# PIC18f26k40_W5500_DevBoard.net
KiCad netlist of a schematic drawn in EAGLE
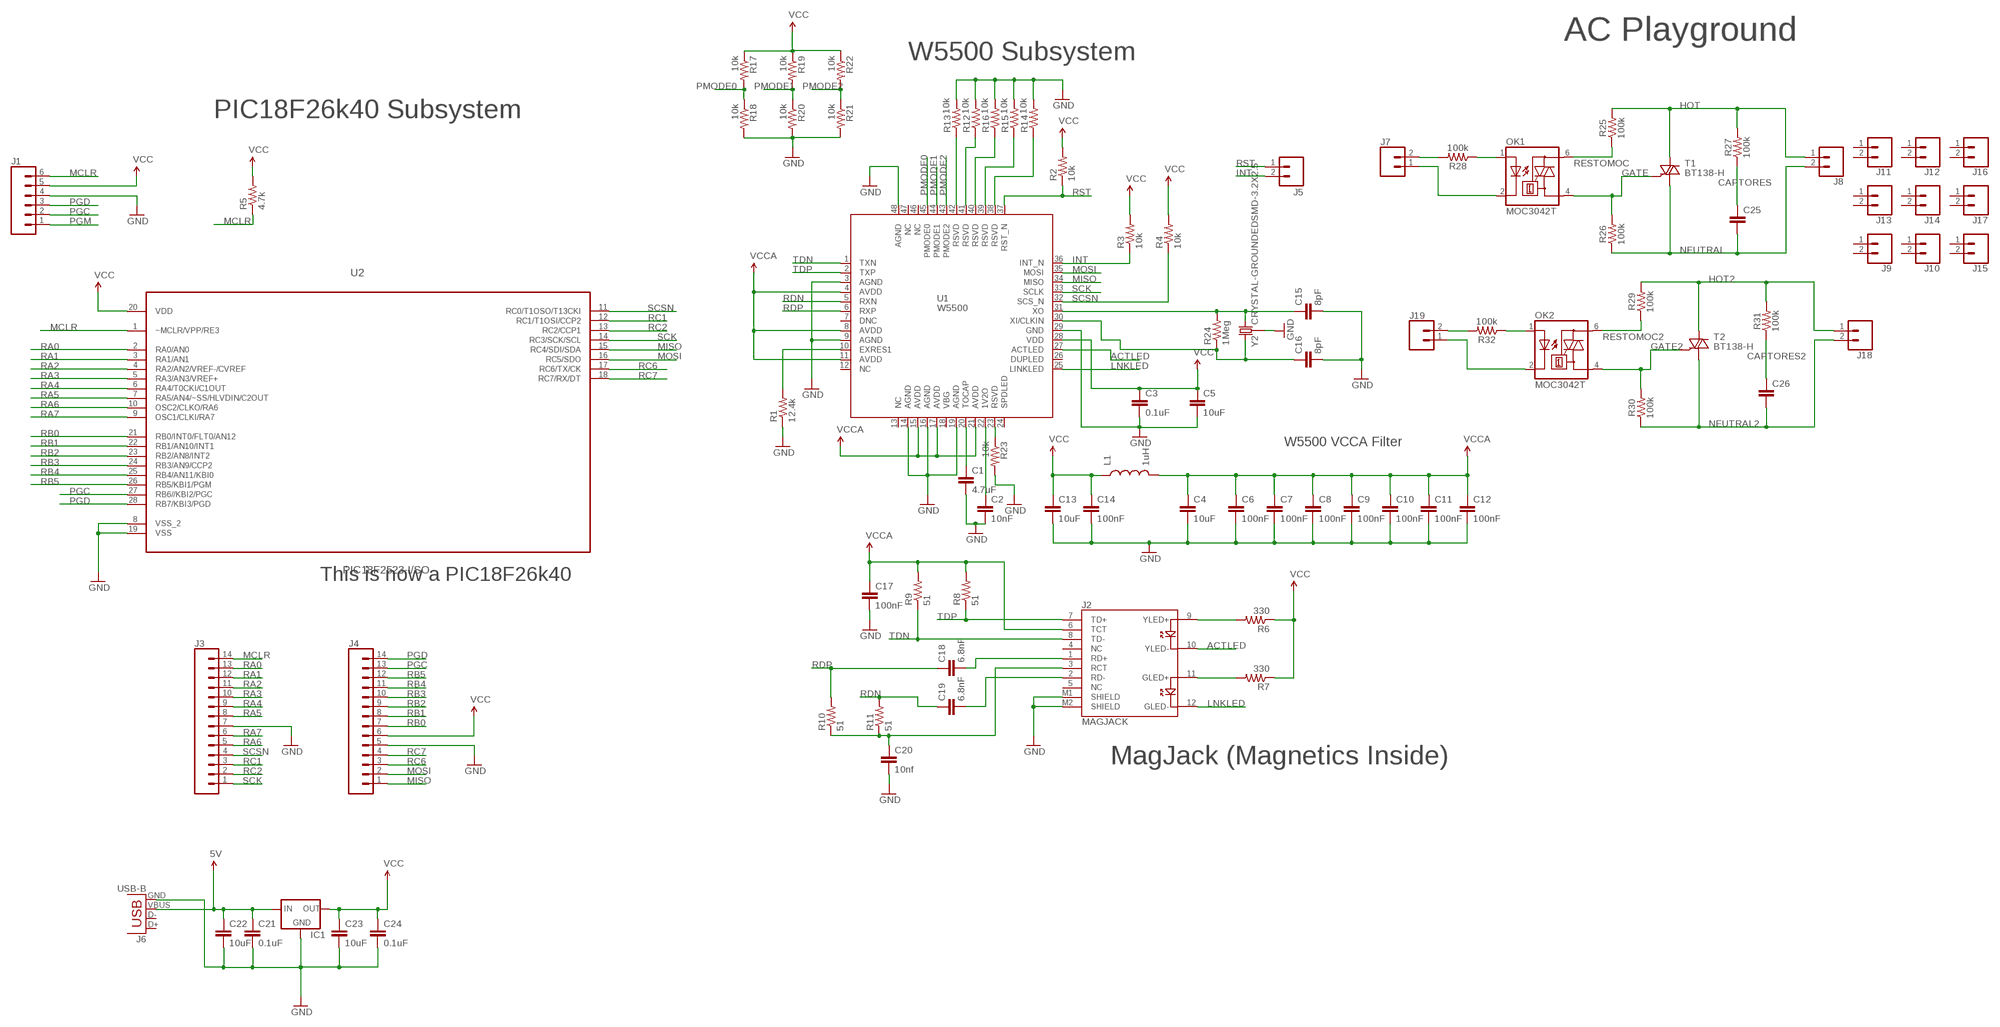
[diagram p0: schematic, sheet 1]

(export (version "E")
  (design (tool "Eeschema 10.0.6"))
  (components
    (comp (ref "C1")
      (value "4.7uF")
      (footprint "eagle-import:0603-CAP")
      (libsource (lib "eagle-import") (part "SparkFun-Passives_CAP0603-CAP"))
    )
    (comp (ref "C2")
      (value "10nF")
      (footprint "eagle-import:0603-CAP")
      (libsource (lib "eagle-import") (part "SparkFun-Passives_CAP0603-CAP"))
    )
    (comp (ref "C3")
      (value "0.1uF")
      (footprint "eagle-import:0603-CAP")
      (libsource (lib "eagle-import") (part "SparkFun-Passives_CAP0603-CAP"))
    )
    (comp (ref "C4")
      (value "10uF")
      (footprint "eagle-import:0603-CAP")
      (libsource (lib "eagle-import") (part "SparkFun-Passives_CAP0603-CAP"))
    )
    (comp (ref "C5")
      (value "10uF")
      (footprint "eagle-import:0603-CAP")
      (libsource (lib "eagle-import") (part "SparkFun-Passives_CAP0603-CAP"))
    )
    (comp (ref "C6")
      (value "100nF")
      (footprint "eagle-import:0603-CAP")
      (libsource (lib "eagle-import") (part "SparkFun-Passives_CAP0603-CAP"))
    )
    (comp (ref "C7")
      (value "100nF")
      (footprint "eagle-import:0603-CAP")
      (libsource (lib "eagle-import") (part "SparkFun-Passives_CAP0603-CAP"))
    )
    (comp (ref "C8")
      (value "100nF")
      (footprint "eagle-import:0603-CAP")
      (libsource (lib "eagle-import") (part "SparkFun-Passives_CAP0603-CAP"))
    )
    (comp (ref "C9")
      (value "100nF")
      (footprint "eagle-import:0603-CAP")
      (libsource (lib "eagle-import") (part "SparkFun-Passives_CAP0603-CAP"))
    )
    (comp (ref "C10")
      (value "100nF")
      (footprint "eagle-import:0603-CAP")
      (libsource (lib "eagle-import") (part "SparkFun-Passives_CAP0603-CAP"))
    )
    (comp (ref "C11")
      (value "100nF")
      (footprint "eagle-import:0603-CAP")
      (libsource (lib "eagle-import") (part "SparkFun-Passives_CAP0603-CAP"))
    )
    (comp (ref "C12")
      (value "100nF")
      (footprint "eagle-import:0603-CAP")
      (libsource (lib "eagle-import") (part "SparkFun-Passives_CAP0603-CAP"))
    )
    (comp (ref "C13")
      (value "10uF")
      (footprint "eagle-import:0603-CAP")
      (libsource (lib "eagle-import") (part "SparkFun-Passives_CAP0603-CAP"))
    )
    (comp (ref "C14")
      (value "100nF")
      (footprint "eagle-import:0603-CAP")
      (libsource (lib "eagle-import") (part "SparkFun-Passives_CAP0603-CAP"))
    )
    (comp (ref "C15")
      (value "8pF")
      (footprint "eagle-import:0603-CAP")
      (libsource (lib "eagle-import") (part "SparkFun-Passives_CAP0603-CAP"))
    )
    (comp (ref "C16")
      (value "8pF")
      (footprint "eagle-import:0603-CAP")
      (libsource (lib "eagle-import") (part "SparkFun-Passives_CAP0603-CAP"))
    )
    (comp (ref "C17")
      (value "100nF")
      (footprint "eagle-import:0603-CAP")
      (libsource (lib "eagle-import") (part "SparkFun-Passives_CAP0603-CAP"))
    )
    (comp (ref "C18")
      (value "6.8nF")
      (footprint "eagle-import:0603-CAP")
      (libsource (lib "eagle-import") (part "SparkFun-Passives_CAP0603-CAP"))
    )
    (comp (ref "C19")
      (value "6.8nF")
      (footprint "eagle-import:0603-CAP")
      (libsource (lib "eagle-import") (part "SparkFun-Passives_CAP0603-CAP"))
    )
    (comp (ref "C20")
      (value "10nf")
      (footprint "eagle-import:0603-CAP")
      (libsource (lib "eagle-import") (part "SparkFun-Passives_CAP0603-CAP"))
    )
    (comp (ref "C21")
      (value "0.1uF")
      (footprint "eagle-import:0603-CAP")
      (libsource (lib "eagle-import") (part "SparkFun-Passives_CAP0603-CAP"))
    )
    (comp (ref "C22")
      (value "10uF")
      (footprint "eagle-import:0603-CAP")
      (libsource (lib "eagle-import") (part "SparkFun-Passives_CAP0603-CAP"))
    )
    (comp (ref "C23")
      (value "10uF")
      (footprint "eagle-import:0603-CAP")
      (libsource (lib "eagle-import") (part "SparkFun-Passives_CAP0603-CAP"))
    )
    (comp (ref "C24")
      (value "0.1uF")
      (footprint "eagle-import:0603-CAP")
      (libsource (lib "eagle-import") (part "SparkFun-Passives_CAP0603-CAP"))
    )
    (comp (ref "C25")
      (value "CAPPTH3")
      (footprint "eagle-import:CAP-PTH-LARGE")
      (libsource (lib "eagle-import") (part "CAPPTH3"))
    )
    (comp (ref "C26")
      (value "CAPPTH3")
      (footprint "eagle-import:CAP-PTH-LARGE")
      (libsource (lib "eagle-import") (part "CAPPTH3"))
    )
    (comp (ref "IC1")
      (value "78XXL")
      (footprint "eagle-import:78XXL")
      (libsource (lib "eagle-import") (part "78XXL"))
    )
    (comp (ref "J1")
      (value "CONN_06NO_SILK_FEMALE_PTH")
      (footprint "eagle-import:1X06_NO_SILK")
      (libsource (lib "eagle-import") (part "CONN_06NO_SILK_FEMALE_PTH"))
    )
    (comp (ref "J2")
      (value "MAGJACK")
      (footprint "eagle-import:MAGJACK")
      (libsource (lib "eagle-import") (part "MAGJACK"))
    )
    (comp (ref "J3")
      (value "CONN_14")
      (footprint "eagle-import:1X14")
      (libsource (lib "eagle-import") (part "CONN_14"))
    )
    (comp (ref "J4")
      (value "CONN_14")
      (footprint "eagle-import:1X14")
      (libsource (lib "eagle-import") (part "CONN_14"))
    )
    (comp (ref "J5")
      (value "M02PTH")
      (footprint "eagle-import:1X02@1")
      (libsource (lib "eagle-import") (part "M02PTH"))
    )
    (comp (ref "J6")
      (value "USB-B")
      (footprint "eagle-import:USB-B-PTH")
      (libsource (lib "eagle-import") (part "USBPTH"))
    )
    (comp (ref "J7")
      (value "CONN_02")
      (footprint "eagle-import:1X02")
      (libsource (lib "eagle-import") (part "CONN_02"))
    )
    (comp (ref "J8")
      (value "CONN_025MM")
      (footprint "eagle-import:SCREWTERMINAL-5MM-2")
      (libsource (lib "eagle-import") (part "CONN_025MM"))
    )
    (comp (ref "J9")
      (value "CONN_025MM")
      (footprint "eagle-import:SCREWTERMINAL-5MM-2")
      (libsource (lib "eagle-import") (part "CONN_025MM"))
    )
    (comp (ref "J10")
      (value "CONN_025MM")
      (footprint "eagle-import:SCREWTERMINAL-5MM-2")
      (libsource (lib "eagle-import") (part "CONN_025MM"))
    )
    (comp (ref "J11")
      (value "CONN_025MM")
      (footprint "eagle-import:SCREWTERMINAL-5MM-2")
      (libsource (lib "eagle-import") (part "CONN_025MM"))
    )
    (comp (ref "J12")
      (value "CONN_025MM")
      (footprint "eagle-import:SCREWTERMINAL-5MM-2")
      (libsource (lib "eagle-import") (part "CONN_025MM"))
    )
    (comp (ref "J13")
      (value "CONN_025MM")
      (footprint "eagle-import:SCREWTERMINAL-5MM-2")
      (libsource (lib "eagle-import") (part "CONN_025MM"))
    )
    (comp (ref "J14")
      (value "CONN_025MM")
      (footprint "eagle-import:SCREWTERMINAL-5MM-2")
      (libsource (lib "eagle-import") (part "CONN_025MM"))
    )
    (comp (ref "J15")
      (value "CONN_025MM")
      (footprint "eagle-import:SCREWTERMINAL-5MM-2")
      (libsource (lib "eagle-import") (part "CONN_025MM"))
    )
    (comp (ref "J16")
      (value "CONN_025MM")
      (footprint "eagle-import:SCREWTERMINAL-5MM-2")
      (libsource (lib "eagle-import") (part "CONN_025MM"))
    )
    (comp (ref "J17")
      (value "CONN_025MM")
      (footprint "eagle-import:SCREWTERMINAL-5MM-2")
      (libsource (lib "eagle-import") (part "CONN_025MM"))
    )
    (comp (ref "J18")
      (value "CONN_025MM")
      (footprint "eagle-import:SCREWTERMINAL-5MM-2")
      (libsource (lib "eagle-import") (part "CONN_025MM"))
    )
    (comp (ref "J19")
      (value "CONN_02")
      (footprint "eagle-import:1X02")
      (libsource (lib "eagle-import") (part "CONN_02"))
    )
    (comp (ref "L1")
      (value "1uH")
      (footprint "eagle-import:0603")
      (libsource (lib "eagle-import") (part "INDUCTOR0603"))
    )
    (comp (ref "OK1")
      (value "MOC3042T")
      (footprint "eagle-import:DIL06B")
      (libsource (lib "eagle-import") (part "MOC30T42"))
    )
    (comp (ref "OK2")
      (value "MOC3042T")
      (footprint "eagle-import:DIL06B")
      (libsource (lib "eagle-import") (part "MOC30T42"))
    )
    (comp (ref "R1")
      (value "12.4k")
      (footprint "eagle-import:0603-RES")
      (libsource (lib "eagle-import") (part "RESISTOR0603-RES"))
    )
    (comp (ref "R2")
      (value "10k")
      (footprint "eagle-import:0603-RES")
      (libsource (lib "eagle-import") (part "RESISTOR0603-RES"))
    )
    (comp (ref "R3")
      (value "10k")
      (footprint "eagle-import:0603-RES")
      (libsource (lib "eagle-import") (part "RESISTOR0603-RES"))
    )
    (comp (ref "R4")
      (value "10k")
      (footprint "eagle-import:0603-RES")
      (libsource (lib "eagle-import") (part "RESISTOR0603-RES"))
    )
    (comp (ref "R5")
      (value "4.7k")
      (footprint "eagle-import:0603-RES")
      (libsource (lib "eagle-import") (part "RESISTOR0603-RES"))
    )
    (comp (ref "R6")
      (value "330")
      (footprint "eagle-import:0603-RES")
      (libsource (lib "eagle-import") (part "RESISTOR0603-RES"))
    )
    (comp (ref "R7")
      (value "330")
      (footprint "eagle-import:0603-RES")
      (libsource (lib "eagle-import") (part "RESISTOR0603-RES"))
    )
    (comp (ref "R8")
      (value "51")
      (footprint "eagle-import:0603-RES")
      (libsource (lib "eagle-import") (part "RESISTOR0603-RES"))
    )
    (comp (ref "R9")
      (value "51")
      (footprint "eagle-import:0603-RES")
      (libsource (lib "eagle-import") (part "RESISTOR0603-RES"))
    )
    (comp (ref "R10")
      (value "51")
      (footprint "eagle-import:0603-RES")
      (libsource (lib "eagle-import") (part "RESISTOR0603-RES"))
    )
    (comp (ref "R11")
      (value "51")
      (footprint "eagle-import:0603-RES")
      (libsource (lib "eagle-import") (part "RESISTOR0603-RES"))
    )
    (comp (ref "R12")
      (value "10k")
      (footprint "eagle-import:0603-RES")
      (libsource (lib "eagle-import") (part "RESISTOR0603-RES"))
    )
    (comp (ref "R13")
      (value "10k")
      (footprint "eagle-import:0603-RES")
      (libsource (lib "eagle-import") (part "RESISTOR0603-RES"))
    )
    (comp (ref "R14")
      (value "10k")
      (footprint "eagle-import:0603-RES")
      (libsource (lib "eagle-import") (part "RESISTOR0603-RES"))
    )
    (comp (ref "R15")
      (value "10k")
      (footprint "eagle-import:0603-RES")
      (libsource (lib "eagle-import") (part "RESISTOR0603-RES"))
    )
    (comp (ref "R16")
      (value "10k")
      (footprint "eagle-import:0603-RES")
      (libsource (lib "eagle-import") (part "RESISTOR0603-RES"))
    )
    (comp (ref "R17")
      (value "10k")
      (footprint "eagle-import:0603-RES")
      (libsource (lib "eagle-import") (part "RESISTOR0603-RES"))
    )
    (comp (ref "R18")
      (value "10k")
      (footprint "eagle-import:0603-RES")
      (libsource (lib "eagle-import") (part "RESISTOR0603-RES"))
    )
    (comp (ref "R19")
      (value "10k")
      (footprint "eagle-import:0603-RES")
      (libsource (lib "eagle-import") (part "RESISTOR0603-RES"))
    )
    (comp (ref "R20")
      (value "10k")
      (footprint "eagle-import:0603-RES")
      (libsource (lib "eagle-import") (part "RESISTOR0603-RES"))
    )
    (comp (ref "R21")
      (value "10k")
      (footprint "eagle-import:0603-RES")
      (libsource (lib "eagle-import") (part "RESISTOR0603-RES"))
    )
    (comp (ref "R22")
      (value "10k")
      (footprint "eagle-import:0603-RES")
      (libsource (lib "eagle-import") (part "RESISTOR0603-RES"))
    )
    (comp (ref "R23")
      (value "10k")
      (footprint "eagle-import:0603-RES")
      (libsource (lib "eagle-import") (part "RESISTOR0603-RES"))
    )
    (comp (ref "R24")
      (value "1Meg")
      (footprint "eagle-import:0603-RES")
      (libsource (lib "eagle-import") (part "RESISTOR0603-RES"))
    )
    (comp (ref "R25")
      (value "100k")
      (footprint "eagle-import:AXIAL-0.3")
      (libsource (lib "eagle-import") (part "100KOHM-HORIZ-1/4W-1%"))
    )
    (comp (ref "R26")
      (value "100k")
      (footprint "eagle-import:AXIAL-0.3")
      (libsource (lib "eagle-import") (part "100KOHM-HORIZ-1/4W-1%"))
    )
    (comp (ref "R27")
      (value "100k")
      (footprint "eagle-import:AXIAL-0.3")
      (libsource (lib "eagle-import") (part "100KOHM-HORIZ-1/4W-1%"))
    )
    (comp (ref "R28")
      (value "100k")
      (footprint "eagle-import:AXIAL-0.3")
      (libsource (lib "eagle-import") (part "100KOHM-HORIZ-1/4W-1%"))
    )
    (comp (ref "R29")
      (value "100k")
      (footprint "eagle-import:AXIAL-0.3")
      (libsource (lib "eagle-import") (part "100KOHM-HORIZ-1/4W-1%"))
    )
    (comp (ref "R30")
      (value "100k")
      (footprint "eagle-import:AXIAL-0.3")
      (libsource (lib "eagle-import") (part "100KOHM-HORIZ-1/4W-1%"))
    )
    (comp (ref "R31")
      (value "100k")
      (footprint "eagle-import:AXIAL-0.3")
      (libsource (lib "eagle-import") (part "100KOHM-HORIZ-1/4W-1%"))
    )
    (comp (ref "R32")
      (value "100k")
      (footprint "eagle-import:AXIAL-0.3")
      (libsource (lib "eagle-import") (part "100KOHM-HORIZ-1/4W-1%"))
    )
    (comp (ref "T1")
      (value "BT138-H")
      (footprint "eagle-import:TO220BH")
      (libsource (lib "eagle-import") (part "BT138-H"))
    )
    (comp (ref "T2")
      (value "BT138-H")
      (footprint "eagle-import:TO220BH")
      (libsource (lib "eagle-import") (part "BT138-H"))
    )
    (comp (ref "U1")
      (value "W5500")
      (footprint "eagle-import:W5500")
      (libsource (lib "eagle-import") (part "W5500"))
    )
    (comp (ref "U2")
      (value "PIC18F2523-I/SO")
      (footprint "eagle-import:SOIC127P1030X265-28N")
      (libsource (lib "eagle-import") (part "PIC18F2523-I/SO"))
    )
    (comp (ref "Y2")
      (value "CRYSTAL-GROUNDEDSMD-3.2X2.5")
      (footprint "eagle-import:CRYSTAL-SMD-3.2X2.5MM")
      (libsource (lib "eagle-import") (part "CRYSTAL-GROUNDEDSMD-3.2X2.5"))
    )
  )
  (nets
    (net (code "1") (name "/ACTLED") (class "Default")
      (node (ref "J2") (pin "10") (pinfunction "YLED-_10") (pintype "bidirectional"))
      (node (ref "U1") (pin "27") (pinfunction "ACTLED_27") (pintype "passive"))
    )
    (net (code "2") (name "/CAPTORES") (class "Default")
      (node (ref "C25") (pin "1") (pinfunction "1_1") (pintype "passive"))
      (node (ref "R27") (pin "P$1") (pinfunction "1_P$1") (pintype "passive"))
    )
    (net (code "3") (name "/CAPTORES2") (class "Default")
      (node (ref "C26") (pin "1") (pinfunction "1_1") (pintype "passive"))
      (node (ref "R31") (pin "P$1") (pinfunction "1_P$1") (pintype "passive"))
    )
    (net (code "4") (name "/GATE") (class "Default")
      (node (ref "OK1") (pin "4") (pinfunction "A1_4") (pintype "passive"))
      (node (ref "R26") (pin "P$2") (pinfunction "2_P$2") (pintype "passive"))
      (node (ref "T1") (pin "G") (pinfunction "G_G") (pintype "passive"))
    )
    (net (code "5") (name "/GATE2") (class "Default")
      (node (ref "OK2") (pin "4") (pinfunction "A1_4") (pintype "passive"))
      (node (ref "R30") (pin "P$2") (pinfunction "2_P$2") (pintype "passive"))
      (node (ref "T2") (pin "G") (pinfunction "G_G") (pintype "passive"))
    )
    (net (code "6") (name "/HOT") (class "Default")
      (node (ref "J8") (pin "1") (pinfunction "1_1") (pintype "passive"))
      (node (ref "R25") (pin "P$2") (pinfunction "2_P$2") (pintype "passive"))
      (node (ref "R27") (pin "P$2") (pinfunction "2_P$2") (pintype "passive"))
      (node (ref "T1") (pin "T2") (pinfunction "A2_T2") (pintype "passive"))
    )
    (net (code "7") (name "/HOT2") (class "Default")
      (node (ref "J18") (pin "1") (pinfunction "1_1") (pintype "passive"))
      (node (ref "R29") (pin "P$2") (pinfunction "2_P$2") (pintype "passive"))
      (node (ref "R31") (pin "P$2") (pinfunction "2_P$2") (pintype "passive"))
      (node (ref "T2") (pin "T2") (pinfunction "A2_T2") (pintype "passive"))
    )
    (net (code "8") (name "/INT") (class "Default")
      (node (ref "J5") (pin "2") (pinfunction "2_2") (pintype "passive"))
      (node (ref "R3") (pin "1") (pinfunction "1_1") (pintype "passive"))
      (node (ref "U1") (pin "36") (pinfunction "INT_N_36") (pintype "passive"))
    )
    (net (code "9") (name "/LNKLED") (class "Default")
      (node (ref "J2") (pin "12") (pinfunction "GLED-_12") (pintype "bidirectional"))
      (node (ref "U1") (pin "25") (pinfunction "LINKLED_25") (pintype "passive"))
    )
    (net (code "10") (name "/MCLR") (class "Default")
      (node (ref "J1") (pin "6") (pinfunction "6_6") (pintype "passive"))
      (node (ref "J3") (pin "14") (pinfunction "14_14") (pintype "passive"))
      (node (ref "R5") (pin "1") (pinfunction "1_1") (pintype "passive"))
      (node (ref "U2") (pin "1") (pinfunction "~{MCLR/VPP/RE3}_1") (pintype "input"))
    )
    (net (code "11") (name "/MISO") (class "Default")
      (node (ref "J4") (pin "1") (pinfunction "1_1") (pintype "passive"))
      (node (ref "U1") (pin "34") (pinfunction "MISO_34") (pintype "passive"))
      (node (ref "U2") (pin "15") (pinfunction "RC4/SDI/SDA_15") (pintype "bidirectional"))
    )
    (net (code "12") (name "/MOSI") (class "Default")
      (node (ref "J4") (pin "2") (pinfunction "2_2") (pintype "passive"))
      (node (ref "U1") (pin "35") (pinfunction "MOSI_35") (pintype "passive"))
      (node (ref "U2") (pin "16") (pinfunction "RC5/SDO_16") (pintype "bidirectional"))
    )
    (net (code "13") (name "/NEUTRAL") (class "Default")
      (node (ref "C25") (pin "2") (pinfunction "2_2") (pintype "passive"))
      (node (ref "J8") (pin "2") (pinfunction "2_2") (pintype "passive"))
      (node (ref "R26") (pin "P$1") (pinfunction "1_P$1") (pintype "passive"))
      (node (ref "T1") (pin "T1") (pinfunction "A1_T1") (pintype "passive"))
    )
    (net (code "14") (name "/NEUTRAL2") (class "Default")
      (node (ref "C26") (pin "2") (pinfunction "2_2") (pintype "passive"))
      (node (ref "J18") (pin "2") (pinfunction "2_2") (pintype "passive"))
      (node (ref "R30") (pin "P$1") (pinfunction "1_P$1") (pintype "passive"))
      (node (ref "T2") (pin "T1") (pinfunction "A1_T1") (pintype "passive"))
    )
    (net (code "15") (name "/PGC") (class "Default")
      (node (ref "J1") (pin "2") (pinfunction "2_2") (pintype "passive"))
      (node (ref "J4") (pin "13") (pinfunction "13_13") (pintype "passive"))
      (node (ref "U2") (pin "27") (pinfunction "RB6//KBI2/PGC_27") (pintype "bidirectional"))
    )
    (net (code "16") (name "/PGD") (class "Default")
      (node (ref "J1") (pin "3") (pinfunction "3_3") (pintype "passive"))
      (node (ref "J4") (pin "14") (pinfunction "14_14") (pintype "passive"))
      (node (ref "U2") (pin "28") (pinfunction "RB7/KBI3/PGD_28") (pintype "bidirectional"))
    )
    (net (code "17") (name "/PGM") (class "Default")
      (node (ref "J1") (pin "1") (pinfunction "1_1") (pintype "passive"))
    )
    (net (code "18") (name "/PMODE0") (class "Default")
      (node (ref "R17") (pin "2") (pinfunction "2_2") (pintype "passive"))
      (node (ref "R18") (pin "1") (pinfunction "1_1") (pintype "passive"))
      (node (ref "U1") (pin "45") (pinfunction "PMODE0_45") (pintype "passive"))
    )
    (net (code "19") (name "/PMODE1") (class "Default")
      (node (ref "R19") (pin "2") (pinfunction "2_2") (pintype "passive"))
      (node (ref "R20") (pin "1") (pinfunction "1_1") (pintype "passive"))
      (node (ref "U1") (pin "44") (pinfunction "PMODE1_44") (pintype "passive"))
    )
    (net (code "20") (name "/PMODE2") (class "Default")
      (node (ref "R21") (pin "1") (pinfunction "1_1") (pintype "passive"))
      (node (ref "R22") (pin "2") (pinfunction "2_2") (pintype "passive"))
      (node (ref "U1") (pin "43") (pinfunction "PMODE2_43") (pintype "passive"))
    )
    (net (code "21") (name "/RA0") (class "Default")
      (node (ref "J3") (pin "13") (pinfunction "13_13") (pintype "passive"))
      (node (ref "U2") (pin "2") (pinfunction "RA0/AN0_2") (pintype "bidirectional"))
    )
    (net (code "22") (name "/RA1") (class "Default")
      (node (ref "J3") (pin "12") (pinfunction "12_12") (pintype "passive"))
      (node (ref "U2") (pin "3") (pinfunction "RA1/AN1_3") (pintype "bidirectional"))
    )
    (net (code "23") (name "/RA2") (class "Default")
      (node (ref "J3") (pin "11") (pinfunction "11_11") (pintype "passive"))
      (node (ref "U2") (pin "4") (pinfunction "RA2/AN2/VREF-/CVREF_4") (pintype "bidirectional"))
    )
    (net (code "24") (name "/RA3") (class "Default")
      (node (ref "J3") (pin "10") (pinfunction "10_10") (pintype "passive"))
      (node (ref "U2") (pin "5") (pinfunction "RA3/AN3/VREF+_5") (pintype "bidirectional"))
    )
    (net (code "25") (name "/RA4") (class "Default")
      (node (ref "J3") (pin "9") (pinfunction "9_9") (pintype "passive"))
      (node (ref "U2") (pin "6") (pinfunction "RA4/T0CKI/C1OUT_6") (pintype "bidirectional"))
    )
    (net (code "26") (name "/RA5") (class "Default")
      (node (ref "J3") (pin "8") (pinfunction "8_8") (pintype "passive"))
      (node (ref "U2") (pin "7") (pinfunction "RA5/AN4/~{SS/HLVDIN/C2OUT}_7") (pintype "bidirectional"))
    )
    (net (code "27") (name "/RA6") (class "Default")
      (node (ref "J3") (pin "5") (pinfunction "5_5") (pintype "passive"))
      (node (ref "U2") (pin "10") (pinfunction "OSC2/CLKO/RA6_10") (pintype "bidirectional"))
    )
    (net (code "28") (name "/RA7") (class "Default")
      (node (ref "J3") (pin "6") (pinfunction "6_6") (pintype "passive"))
      (node (ref "U2") (pin "9") (pinfunction "OSC1/CLKI/RA7_9") (pintype "bidirectional"))
    )
    (net (code "29") (name "/RB0") (class "Default")
      (node (ref "J4") (pin "7") (pinfunction "7_7") (pintype "passive"))
      (node (ref "U2") (pin "21") (pinfunction "RB0/INT0/FLT0/AN12_21") (pintype "bidirectional"))
    )
    (net (code "30") (name "/RB1") (class "Default")
      (node (ref "J4") (pin "8") (pinfunction "8_8") (pintype "passive"))
      (node (ref "U2") (pin "22") (pinfunction "RB1/AN10/INT1_22") (pintype "bidirectional"))
    )
    (net (code "31") (name "/RB2") (class "Default")
      (node (ref "J4") (pin "9") (pinfunction "9_9") (pintype "passive"))
      (node (ref "U2") (pin "23") (pinfunction "RB2/AN8/INT2_23") (pintype "bidirectional"))
    )
    (net (code "32") (name "/RB3") (class "Default")
      (node (ref "J4") (pin "10") (pinfunction "10_10") (pintype "passive"))
      (node (ref "U2") (pin "24") (pinfunction "RB3/AN9/CCP2_24") (pintype "bidirectional"))
    )
    (net (code "33") (name "/RB4") (class "Default")
      (node (ref "J4") (pin "11") (pinfunction "11_11") (pintype "passive"))
      (node (ref "U2") (pin "25") (pinfunction "RB4/AN11/KBI0_25") (pintype "bidirectional"))
    )
    (net (code "34") (name "/RB5") (class "Default")
      (node (ref "J4") (pin "12") (pinfunction "12_12") (pintype "passive"))
      (node (ref "U2") (pin "26") (pinfunction "RB5/KBI1/PGM_26") (pintype "bidirectional"))
    )
    (net (code "35") (name "/RC1") (class "Default")
      (node (ref "J3") (pin "3") (pinfunction "3_3") (pintype "passive"))
      (node (ref "U2") (pin "12") (pinfunction "RC1/T1OSI/CCP2_12") (pintype "bidirectional"))
    )
    (net (code "36") (name "/RC2") (class "Default")
      (node (ref "J3") (pin "2") (pinfunction "2_2") (pintype "passive"))
      (node (ref "U2") (pin "13") (pinfunction "RC2/CCP1_13") (pintype "bidirectional"))
    )
    (net (code "37") (name "/RC6") (class "Default")
      (node (ref "J4") (pin "3") (pinfunction "3_3") (pintype "passive"))
      (node (ref "U2") (pin "17") (pinfunction "RC6/TX/CK_17") (pintype "bidirectional"))
    )
    (net (code "38") (name "/RC7") (class "Default")
      (node (ref "J4") (pin "4") (pinfunction "4_4") (pintype "passive"))
      (node (ref "U2") (pin "18") (pinfunction "RC7/RX/DT_18") (pintype "bidirectional"))
    )
    (net (code "39") (name "/RDN") (class "Default")
      (node (ref "C19") (pin "1") (pinfunction "1_1") (pintype "passive"))
      (node (ref "R11") (pin "2") (pinfunction "2_2") (pintype "passive"))
      (node (ref "U1") (pin "5") (pinfunction "RXN_5") (pintype "passive"))
    )
    (net (code "40") (name "/RDP") (class "Default")
      (node (ref "C18") (pin "1") (pinfunction "1_1") (pintype "passive"))
      (node (ref "R10") (pin "2") (pinfunction "2_2") (pintype "passive"))
      (node (ref "U1") (pin "6") (pinfunction "RXP_6") (pintype "passive"))
    )
    (net (code "41") (name "/RESTOMOC") (class "Default")
      (node (ref "OK1") (pin "6") (pinfunction "A2_6") (pintype "passive"))
      (node (ref "R25") (pin "P$1") (pinfunction "1_P$1") (pintype "passive"))
    )
    (net (code "42") (name "/RESTOMOC2") (class "Default")
      (node (ref "OK2") (pin "6") (pinfunction "A2_6") (pintype "passive"))
      (node (ref "R29") (pin "P$1") (pinfunction "1_P$1") (pintype "passive"))
    )
    (net (code "43") (name "/RST") (class "Default")
      (node (ref "J5") (pin "1") (pinfunction "1_1") (pintype "passive"))
      (node (ref "R2") (pin "1") (pinfunction "1_1") (pintype "passive"))
      (node (ref "U1") (pin "37") (pinfunction "RST_N_37") (pintype "passive"))
    )
    (net (code "44") (name "/SCK") (class "Default")
      (node (ref "J3") (pin "1") (pinfunction "1_1") (pintype "passive"))
      (node (ref "U1") (pin "33") (pinfunction "SCLK_33") (pintype "passive"))
      (node (ref "U2") (pin "14") (pinfunction "RC3/SCK/SCL_14") (pintype "bidirectional"))
    )
    (net (code "45") (name "/SCSN") (class "Default")
      (node (ref "J3") (pin "4") (pinfunction "4_4") (pintype "passive"))
      (node (ref "R4") (pin "1") (pinfunction "1_1") (pintype "passive"))
      (node (ref "U1") (pin "32") (pinfunction "SCS_N_32") (pintype "passive"))
      (node (ref "U2") (pin "11") (pinfunction "RC0/T1OSO/T13CKI_11") (pintype "bidirectional"))
    )
    (net (code "46") (name "/TDN") (class "Default")
      (node (ref "J2") (pin "8") (pinfunction "TD-_8") (pintype "bidirectional"))
      (node (ref "R9") (pin "1") (pinfunction "1_1") (pintype "passive"))
      (node (ref "U1") (pin "1") (pinfunction "TXN_1") (pintype "passive"))
    )
    (net (code "47") (name "/TDP") (class "Default")
      (node (ref "J2") (pin "7") (pinfunction "TD+_7") (pintype "bidirectional"))
      (node (ref "R8") (pin "1") (pinfunction "1_1") (pintype "passive"))
      (node (ref "U1") (pin "2") (pinfunction "TXP_2") (pintype "passive"))
    )
    (net (code "48") (name "5V") (class "Default")
      (node (ref "C21") (pin "1") (pinfunction "1_1") (pintype "passive"))
      (node (ref "C22") (pin "1") (pinfunction "1_1") (pintype "passive"))
      (node (ref "IC1") (pin "IN") (pinfunction "IN_IN") (pintype "input"))
      (node (ref "J6") (pin "VBUS") (pinfunction "VBUS_VBUS") (pintype "bidirectional"))
    )
    (net (code "49") (name "GND") (class "Default")
      (node (ref "C1") (pin "2") (pinfunction "2_2") (pintype "passive"))
      (node (ref "C10") (pin "2") (pinfunction "2_2") (pintype "passive"))
      (node (ref "C11") (pin "2") (pinfunction "2_2") (pintype "passive"))
      (node (ref "C12") (pin "2") (pinfunction "2_2") (pintype "passive"))
      (node (ref "C13") (pin "2") (pinfunction "2_2") (pintype "passive"))
      (node (ref "C14") (pin "2") (pinfunction "2_2") (pintype "passive"))
      (node (ref "C15") (pin "2") (pinfunction "2_2") (pintype "passive"))
      (node (ref "C16") (pin "2") (pinfunction "2_2") (pintype "passive"))
      (node (ref "C17") (pin "2") (pinfunction "2_2") (pintype "passive"))
      (node (ref "C2") (pin "2") (pinfunction "2_2") (pintype "passive"))
      (node (ref "C20") (pin "2") (pinfunction "2_2") (pintype "passive"))
      (node (ref "C21") (pin "2") (pinfunction "2_2") (pintype "passive"))
      (node (ref "C22") (pin "2") (pinfunction "2_2") (pintype "passive"))
      (node (ref "C23") (pin "2") (pinfunction "2_2") (pintype "passive"))
      (node (ref "C24") (pin "2") (pinfunction "2_2") (pintype "passive"))
      (node (ref "C3") (pin "2") (pinfunction "2_2") (pintype "passive"))
      (node (ref "C4") (pin "2") (pinfunction "2_2") (pintype "passive"))
      (node (ref "C5") (pin "2") (pinfunction "2_2") (pintype "passive"))
      (node (ref "C6") (pin "2") (pinfunction "2_2") (pintype "passive"))
      (node (ref "C7") (pin "2") (pinfunction "2_2") (pintype "passive"))
      (node (ref "C8") (pin "2") (pinfunction "2_2") (pintype "passive"))
      (node (ref "C9") (pin "2") (pinfunction "2_2") (pintype "passive"))
      (node (ref "IC1") (pin "GND") (pinfunction "GND_GND") (pintype "input"))
      (node (ref "J1") (pin "4") (pinfunction "4_4") (pintype "passive"))
      (node (ref "J2") (pin "M1") (pinfunction "SHIELD_M1") (pintype "bidirectional"))
      (node (ref "J2") (pin "M2") (pinfunction "SHIELD_M2") (pintype "bidirectional"))
      (node (ref "J3") (pin "7") (pinfunction "7_7") (pintype "passive"))
      (node (ref "J4") (pin "5") (pinfunction "5_5") (pintype "passive"))
      (node (ref "J6") (pin "GND") (pinfunction "GND_GND") (pintype "bidirectional"))
      (node (ref "R1") (pin "1") (pinfunction "1_1") (pintype "passive"))
      (node (ref "R12") (pin "2") (pinfunction "2_2") (pintype "passive"))
      (node (ref "R13") (pin "2") (pinfunction "2_2") (pintype "passive"))
      (node (ref "R14") (pin "2") (pinfunction "2_2") (pintype "passive"))
      (node (ref "R15") (pin "2") (pinfunction "2_2") (pintype "passive"))
      (node (ref "R16") (pin "2") (pinfunction "2_2") (pintype "passive"))
      (node (ref "R18") (pin "2") (pinfunction "2_2") (pintype "passive"))
      (node (ref "R20") (pin "2") (pinfunction "2_2") (pintype "passive"))
      (node (ref "R21") (pin "2") (pinfunction "2_2") (pintype "passive"))
      (node (ref "R23") (pin "2") (pinfunction "2_2") (pintype "passive"))
      (node (ref "U1") (pin "14") (pinfunction "AGND_14") (pintype "passive"))
      (node (ref "U1") (pin "16") (pinfunction "AGND_16") (pintype "passive"))
      (node (ref "U1") (pin "19") (pinfunction "AGND_19") (pintype "passive"))
      (node (ref "U1") (pin "29") (pinfunction "GND_29") (pintype "passive"))
      (node (ref "U1") (pin "3") (pinfunction "AGND_3") (pintype "passive"))
      (node (ref "U1") (pin "48") (pinfunction "AGND_48") (pintype "passive"))
      (node (ref "U1") (pin "9") (pinfunction "AGND_9") (pintype "passive"))
      (node (ref "U2") (pin "19") (pinfunction "VSS_19") (pintype "passive"))
      (node (ref "U2") (pin "8") (pinfunction "VSS_2_8") (pintype "passive"))
      (node (ref "Y2") (pin "2") (pinfunction "3_2") (pintype "passive"))
      (node (ref "Y2") (pin "4") (pinfunction "3_4") (pintype "passive"))
    )
    (net (code "50") (name "Net-(J2-GLED+)") (class "Default")
      (node (ref "J2") (pin "11") (pinfunction "GLED+_11") (pintype "bidirectional"))
      (node (ref "R7") (pin "2") (pinfunction "2_2") (pintype "passive"))
    )
    (net (code "51") (name "Net-(J2-RCT)") (class "Default")
      (node (ref "C20") (pin "1") (pinfunction "1_1") (pintype "passive"))
      (node (ref "J2") (pin "3") (pinfunction "RCT_3") (pintype "bidirectional"))
      (node (ref "R10") (pin "1") (pinfunction "1_1") (pintype "passive"))
      (node (ref "R11") (pin "1") (pinfunction "1_1") (pintype "passive"))
    )
    (net (code "52") (name "Net-(J2-RD+)") (class "Default")
      (node (ref "C18") (pin "2") (pinfunction "2_2") (pintype "passive"))
      (node (ref "J2") (pin "1") (pinfunction "RD+_1") (pintype "bidirectional"))
    )
    (net (code "53") (name "Net-(J2-RD-)") (class "Default")
      (node (ref "C19") (pin "2") (pinfunction "2_2") (pintype "passive"))
      (node (ref "J2") (pin "2") (pinfunction "RD-_2") (pintype "bidirectional"))
    )
    (net (code "54") (name "Net-(J2-YLED+)") (class "Default")
      (node (ref "J2") (pin "9") (pinfunction "YLED+_9") (pintype "bidirectional"))
      (node (ref "R6") (pin "2") (pinfunction "2_2") (pintype "passive"))
    )
    (net (code "55") (name "Net-(OK1-A)") (class "Default")
      (node (ref "OK1") (pin "1") (pinfunction "A_1") (pintype "passive"))
      (node (ref "R28") (pin "P$1") (pinfunction "1_P$1") (pintype "passive"))
    )
    (net (code "56") (name "Net-(OK1-C)") (class "Default")
      (node (ref "J7") (pin "1") (pinfunction "1_1") (pintype "passive"))
      (node (ref "OK1") (pin "2") (pinfunction "C_2") (pintype "passive"))
    )
    (net (code "57") (name "Net-(OK2-A)") (class "Default")
      (node (ref "OK2") (pin "1") (pinfunction "A_1") (pintype "passive"))
      (node (ref "R32") (pin "P$1") (pinfunction "1_P$1") (pintype "passive"))
    )
    (net (code "58") (name "Net-(OK2-C)") (class "Default")
      (node (ref "J19") (pin "1") (pinfunction "1_1") (pintype "passive"))
      (node (ref "OK2") (pin "2") (pinfunction "C_2") (pintype "passive"))
    )
    (net (code "59") (name "Net-(R12-Pad1)") (class "Default")
      (node (ref "R12") (pin "1") (pinfunction "1_1") (pintype "passive"))
      (node (ref "U1") (pin "41") (pinfunction "RSVD_41") (pintype "passive"))
    )
    (net (code "60") (name "Net-(R13-Pad1)") (class "Default")
      (node (ref "R13") (pin "1") (pinfunction "1_1") (pintype "passive"))
      (node (ref "U1") (pin "42") (pinfunction "RSVD_42") (pintype "passive"))
    )
    (net (code "61") (name "Net-(R14-Pad1)") (class "Default")
      (node (ref "R14") (pin "1") (pinfunction "1_1") (pintype "passive"))
      (node (ref "U1") (pin "38") (pinfunction "RSVD_38") (pintype "passive"))
    )
    (net (code "62") (name "Net-(R15-Pad1)") (class "Default")
      (node (ref "R15") (pin "1") (pinfunction "1_1") (pintype "passive"))
      (node (ref "U1") (pin "39") (pinfunction "RSVD_39") (pintype "passive"))
    )
    (net (code "63") (name "Net-(R16-Pad1)") (class "Default")
      (node (ref "R16") (pin "1") (pinfunction "1_1") (pintype "passive"))
      (node (ref "U1") (pin "40") (pinfunction "RSVD_40") (pintype "passive"))
    )
    (net (code "64") (name "Net-(R23-Pad1)") (class "Default")
      (node (ref "R23") (pin "1") (pinfunction "1_1") (pintype "passive"))
      (node (ref "U1") (pin "23") (pinfunction "RSVD_23") (pintype "passive"))
    )
    (net (code "65") (name "Net-(R28-2)") (class "Default")
      (node (ref "J7") (pin "2") (pinfunction "2_2") (pintype "passive"))
      (node (ref "R28") (pin "P$2") (pinfunction "2_P$2") (pintype "passive"))
    )
    (net (code "66") (name "Net-(R32-2)") (class "Default")
      (node (ref "J19") (pin "2") (pinfunction "2_2") (pintype "passive"))
      (node (ref "R32") (pin "P$2") (pinfunction "2_P$2") (pintype "passive"))
    )
    (net (code "67") (name "Net-(U1-1V2O)") (class "Default")
      (node (ref "C2") (pin "1") (pinfunction "1_1") (pintype "passive"))
      (node (ref "U1") (pin "22") (pinfunction "1V2O_22") (pintype "passive"))
    )
    (net (code "68") (name "Net-(U1-EXRES1)") (class "Default")
      (node (ref "R1") (pin "2") (pinfunction "2_2") (pintype "passive"))
      (node (ref "U1") (pin "10") (pinfunction "EXRES1_10") (pintype "passive"))
    )
    (net (code "69") (name "Net-(U1-TOCAP)") (class "Default")
      (node (ref "C1") (pin "1") (pinfunction "1_1") (pintype "passive"))
      (node (ref "U1") (pin "20") (pinfunction "TOCAP_20") (pintype "passive"))
    )
    (net (code "70") (name "Net-(U1-XI{slash}CLKIN)") (class "Default")
      (node (ref "C16") (pin "1") (pinfunction "1_1") (pintype "passive"))
      (node (ref "R24") (pin "1") (pinfunction "1_1") (pintype "passive"))
      (node (ref "U1") (pin "30") (pinfunction "XI/CLKIN_30") (pintype "passive"))
      (node (ref "Y2") (pin "1") (pinfunction "1_1") (pintype "passive"))
    )
    (net (code "71") (name "Net-(U1-XO)") (class "Default")
      (node (ref "C15") (pin "1") (pinfunction "1_1") (pintype "passive"))
      (node (ref "R24") (pin "2") (pinfunction "2_2") (pintype "passive"))
      (node (ref "U1") (pin "31") (pinfunction "XO_31") (pintype "passive"))
      (node (ref "Y2") (pin "3") (pinfunction "2_3") (pintype "passive"))
    )
    (net (code "72") (name "VCC") (class "Default")
      (node (ref "C13") (pin "1") (pinfunction "1_1") (pintype "passive"))
      (node (ref "C14") (pin "1") (pinfunction "1_1") (pintype "passive"))
      (node (ref "C23") (pin "1") (pinfunction "1_1") (pintype "passive"))
      (node (ref "C24") (pin "1") (pinfunction "1_1") (pintype "passive"))
      (node (ref "C3") (pin "1") (pinfunction "1_1") (pintype "passive"))
      (node (ref "C5") (pin "1") (pinfunction "1_1") (pintype "passive"))
      (node (ref "IC1") (pin "OUT") (pinfunction "OUT_OUT") (pintype "passive"))
      (node (ref "J1") (pin "5") (pinfunction "5_5") (pintype "passive"))
      (node (ref "J4") (pin "6") (pinfunction "6_6") (pintype "passive"))
      (node (ref "L1") (pin "1") (pinfunction "1_1") (pintype "passive"))
      (node (ref "R17") (pin "1") (pinfunction "1_1") (pintype "passive"))
      (node (ref "R19") (pin "1") (pinfunction "1_1") (pintype "passive"))
      (node (ref "R2") (pin "2") (pinfunction "2_2") (pintype "passive"))
      (node (ref "R22") (pin "1") (pinfunction "1_1") (pintype "passive"))
      (node (ref "R3") (pin "2") (pinfunction "2_2") (pintype "passive"))
      (node (ref "R4") (pin "2") (pinfunction "2_2") (pintype "passive"))
      (node (ref "R5") (pin "2") (pinfunction "2_2") (pintype "passive"))
      (node (ref "R6") (pin "1") (pinfunction "1_1") (pintype "passive"))
      (node (ref "R7") (pin "1") (pinfunction "1_1") (pintype "passive"))
      (node (ref "U1") (pin "28") (pinfunction "VDD_28") (pintype "passive"))
      (node (ref "U2") (pin "20") (pinfunction "VDD_20") (pintype "power_in"))
    )
    (net (code "73") (name "VCCA") (class "Default")
      (node (ref "C10") (pin "1") (pinfunction "1_1") (pintype "passive"))
      (node (ref "C11") (pin "1") (pinfunction "1_1") (pintype "passive"))
      (node (ref "C12") (pin "1") (pinfunction "1_1") (pintype "passive"))
      (node (ref "C17") (pin "1") (pinfunction "1_1") (pintype "passive"))
      (node (ref "C4") (pin "1") (pinfunction "1_1") (pintype "passive"))
      (node (ref "C6") (pin "1") (pinfunction "1_1") (pintype "passive"))
      (node (ref "C7") (pin "1") (pinfunction "1_1") (pintype "passive"))
      (node (ref "C8") (pin "1") (pinfunction "1_1") (pintype "passive"))
      (node (ref "C9") (pin "1") (pinfunction "1_1") (pintype "passive"))
      (node (ref "J2") (pin "6") (pinfunction "TCT_6") (pintype "bidirectional"))
      (node (ref "L1") (pin "2") (pinfunction "2_2") (pintype "passive"))
      (node (ref "R8") (pin "2") (pinfunction "2_2") (pintype "passive"))
      (node (ref "R9") (pin "2") (pinfunction "2_2") (pintype "passive"))
      (node (ref "U1") (pin "11") (pinfunction "AVDD_11") (pintype "passive"))
      (node (ref "U1") (pin "15") (pinfunction "AVDD_15") (pintype "passive"))
      (node (ref "U1") (pin "17") (pinfunction "AVDD_17") (pintype "passive"))
      (node (ref "U1") (pin "21") (pinfunction "AVDD_21") (pintype "passive"))
      (node (ref "U1") (pin "4") (pinfunction "AVDD_4") (pintype "passive"))
      (node (ref "U1") (pin "8") (pinfunction "AVDD_8") (pintype "passive"))
    )
    (net (code "74") (name "unconnected-(J2-NC-Pad4)") (class "Default")
      (node (ref "J2") (pin "4") (pinfunction "NC_4") (pintype "bidirectional"))
    )
    (net (code "75") (name "unconnected-(J2-NC-Pad5)") (class "Default")
      (node (ref "J2") (pin "5") (pinfunction "NC_5") (pintype "bidirectional"))
    )
    (net (code "76") (name "unconnected-(J6-PadD+)") (class "Default")
      (node (ref "J6") (pin "D+") (pinfunction "D+_D+") (pintype "bidirectional"))
    )
    (net (code "77") (name "unconnected-(J6-PadD-)") (class "Default")
      (node (ref "J6") (pin "D-") (pinfunction "D-_D-") (pintype "bidirectional"))
    )
    (net (code "78") (name "unconnected-(J9-Pad1)") (class "Default")
      (node (ref "J9") (pin "1") (pinfunction "1_1") (pintype "passive"))
    )
    (net (code "79") (name "unconnected-(J9-Pad2)") (class "Default")
      (node (ref "J9") (pin "2") (pinfunction "2_2") (pintype "passive"))
    )
    (net (code "80") (name "unconnected-(J10-Pad1)") (class "Default")
      (node (ref "J10") (pin "1") (pinfunction "1_1") (pintype "passive"))
    )
    (net (code "81") (name "unconnected-(J10-Pad2)") (class "Default")
      (node (ref "J10") (pin "2") (pinfunction "2_2") (pintype "passive"))
    )
    (net (code "82") (name "unconnected-(J11-Pad1)") (class "Default")
      (node (ref "J11") (pin "1") (pinfunction "1_1") (pintype "passive"))
    )
    (net (code "83") (name "unconnected-(J11-Pad2)") (class "Default")
      (node (ref "J11") (pin "2") (pinfunction "2_2") (pintype "passive"))
    )
    (net (code "84") (name "unconnected-(J12-Pad1)") (class "Default")
      (node (ref "J12") (pin "1") (pinfunction "1_1") (pintype "passive"))
    )
    (net (code "85") (name "unconnected-(J12-Pad2)") (class "Default")
      (node (ref "J12") (pin "2") (pinfunction "2_2") (pintype "passive"))
    )
    (net (code "86") (name "unconnected-(J13-Pad1)") (class "Default")
      (node (ref "J13") (pin "1") (pinfunction "1_1") (pintype "passive"))
    )
    (net (code "87") (name "unconnected-(J13-Pad2)") (class "Default")
      (node (ref "J13") (pin "2") (pinfunction "2_2") (pintype "passive"))
    )
    (net (code "88") (name "unconnected-(J14-Pad1)") (class "Default")
      (node (ref "J14") (pin "1") (pinfunction "1_1") (pintype "passive"))
    )
    (net (code "89") (name "unconnected-(J14-Pad2)") (class "Default")
      (node (ref "J14") (pin "2") (pinfunction "2_2") (pintype "passive"))
    )
    (net (code "90") (name "unconnected-(J15-Pad1)") (class "Default")
      (node (ref "J15") (pin "1") (pinfunction "1_1") (pintype "passive"))
    )
    (net (code "91") (name "unconnected-(J15-Pad2)") (class "Default")
      (node (ref "J15") (pin "2") (pinfunction "2_2") (pintype "passive"))
    )
    (net (code "92") (name "unconnected-(J16-Pad1)") (class "Default")
      (node (ref "J16") (pin "1") (pinfunction "1_1") (pintype "passive"))
    )
    (net (code "93") (name "unconnected-(J16-Pad2)") (class "Default")
      (node (ref "J16") (pin "2") (pinfunction "2_2") (pintype "passive"))
    )
    (net (code "94") (name "unconnected-(J17-Pad1)") (class "Default")
      (node (ref "J17") (pin "1") (pinfunction "1_1") (pintype "passive"))
    )
    (net (code "95") (name "unconnected-(J17-Pad2)") (class "Default")
      (node (ref "J17") (pin "2") (pinfunction "2_2") (pintype "passive"))
    )
    (net (code "96") (name "unconnected-(U1-DNC-Pad7)") (class "Default")
      (node (ref "U1") (pin "7") (pinfunction "DNC_7") (pintype "passive"))
    )
    (net (code "97") (name "unconnected-(U1-DUPLED-Pad26)") (class "Default")
      (node (ref "U1") (pin "26") (pinfunction "DUPLED_26") (pintype "passive"))
    )
    (net (code "98") (name "unconnected-(U1-NC-Pad12)") (class "Default")
      (node (ref "U1") (pin "12") (pinfunction "NC_12") (pintype "passive"))
    )
    (net (code "99") (name "unconnected-(U1-NC-Pad13)") (class "Default")
      (node (ref "U1") (pin "13") (pinfunction "NC_13") (pintype "passive"))
    )
    (net (code "100") (name "unconnected-(U1-NC-Pad46)") (class "Default")
      (node (ref "U1") (pin "46") (pinfunction "NC_46") (pintype "passive"))
    )
    (net (code "101") (name "unconnected-(U1-NC-Pad47)") (class "Default")
      (node (ref "U1") (pin "47") (pinfunction "NC_47") (pintype "passive"))
    )
    (net (code "102") (name "unconnected-(U1-SPDLED-Pad24)") (class "Default")
      (node (ref "U1") (pin "24") (pinfunction "SPDLED_24") (pintype "passive"))
    )
    (net (code "103") (name "unconnected-(U1-VBG-Pad18)") (class "Default")
      (node (ref "U1") (pin "18") (pinfunction "VBG_18") (pintype "passive"))
    )
  )
)
